# POWER.net
KiCad netlist of a schematic drawn in Altium Designer
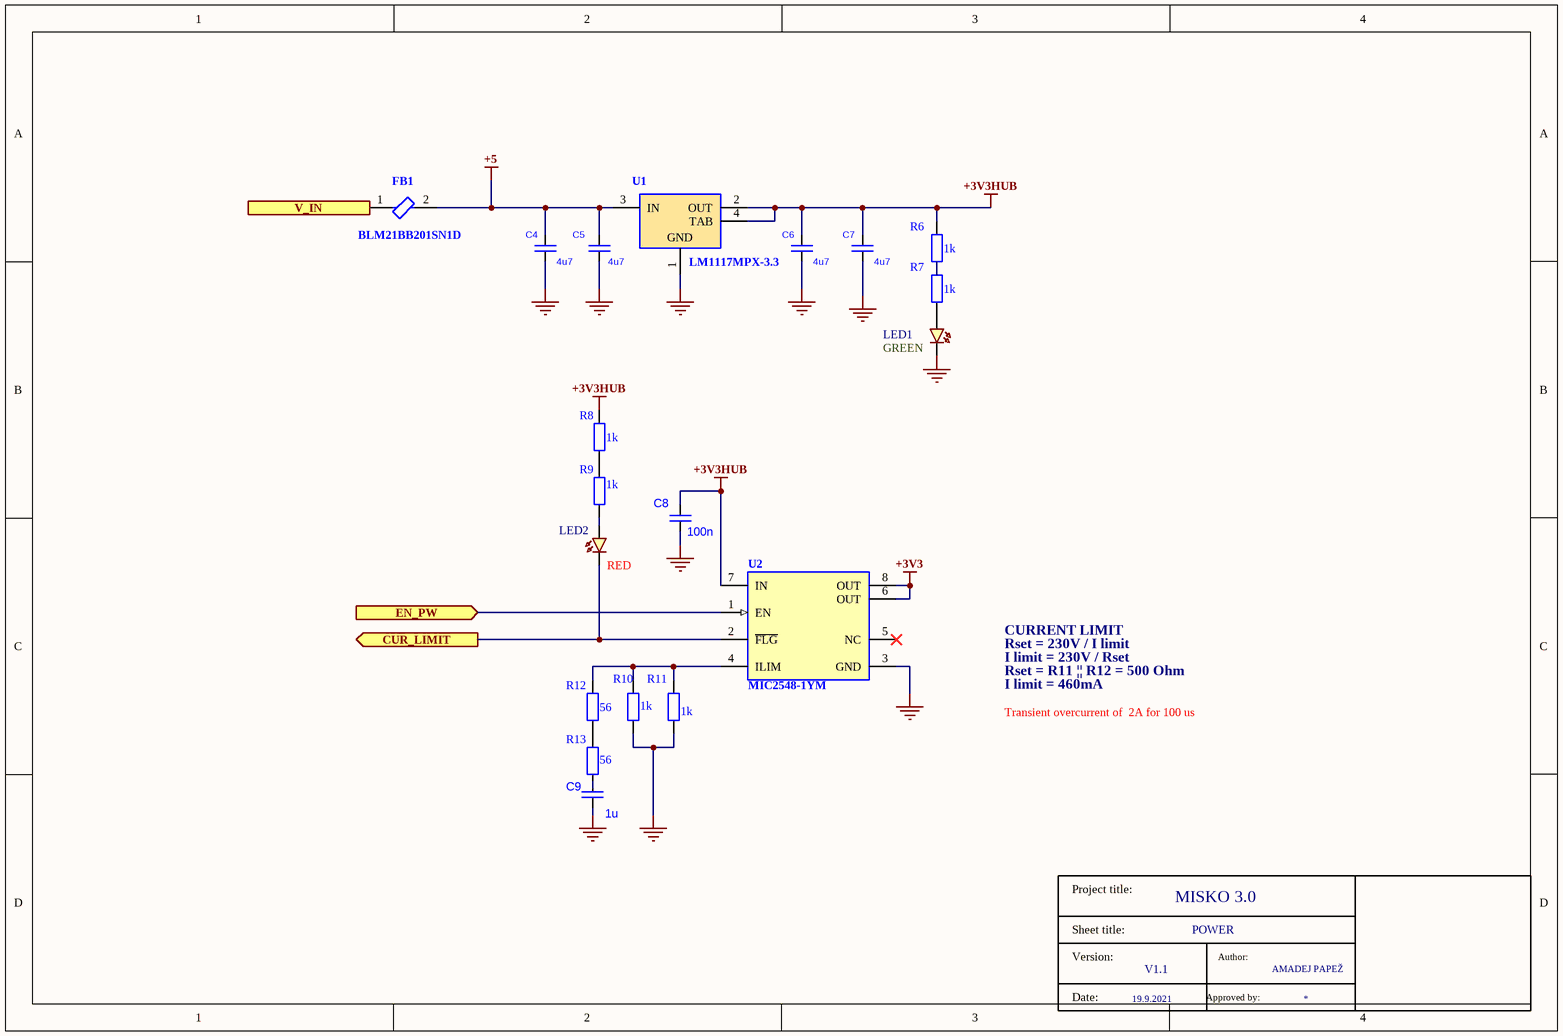
[diagram p0: POWER.SchDoc]

(export (version "E")
  (design (tool "Eeschema 10.0.6"))
  (components
    (comp (ref "C4")
      (value "4u7")
      (footprint "C0603")
      (description "Capacitor")
      (libsource (lib "MISKO3_V6") (part "C"))
    )
    (comp (ref "C5")
      (value "4u7")
      (footprint "C0603")
      (description "Capacitor")
      (libsource (lib "MISKO3_V6") (part "C"))
    )
    (comp (ref "C6")
      (value "4u7")
      (footprint "C0603")
      (description "Capacitor")
      (libsource (lib "MISKO3_V6") (part "C"))
    )
    (comp (ref "C7")
      (value "4u7")
      (footprint "C0603")
      (description "Capacitor")
      (libsource (lib "MISKO3_V6") (part "C"))
    )
    (comp (ref "C8")
      (value "100n")
      (footprint "C0603")
      (description "Capacitor")
      (libsource (lib "MISKO3_V6") (part "C"))
    )
    (comp (ref "C9")
      (value "1u")
      (footprint "C0603")
      (description "Capacitor")
      (libsource (lib "MISKO3_V6") (part "C"))
    )
    (comp (ref "FB1")
      (value "BLM21BB201SN1D")
      (footprint "BLM2102FB0805")
      (description "Chip Ferrite Bead, 0805, 200Ω @ 100MHz, 0.26Ω, 25%, 500mA")
      (fields (field (name "TOLERANCE") "25%"))
      (libsource (lib "MISKO3_V6") (part "BLM21BB201SN1D"))
    )
    (comp (ref "LED1")
      (value "GREEN")
      (footprint "LED0603")
      (description "Green light-emitting diode")
      (libsource (lib "MISKO3_V6") (part "LED"))
    )
    (comp (ref "LED2")
      (value "RED")
      (footprint "LED0603")
      (description "Red light-emitting diode")
      (libsource (lib "MISKO3_V6") (part "LED"))
    )
    (comp (ref "R6")
      (value "1k")
      (footprint "R1608_0603I_L")
      (description "R")
      (libsource (lib "MISKO3_V6") (part "R"))
    )
    (comp (ref "R7")
      (value "1k")
      (footprint "R1608_0603I_L")
      (description "R")
      (libsource (lib "MISKO3_V6") (part "R"))
    )
    (comp (ref "R8")
      (value "1k")
      (footprint "R1608_0603I_L")
      (description "R")
      (libsource (lib "MISKO3_V6") (part "R"))
    )
    (comp (ref "R9")
      (value "1k")
      (footprint "R1608_0603I_L")
      (description "R")
      (libsource (lib "MISKO3_V6") (part "R"))
    )
    (comp (ref "R10")
      (value "1k")
      (footprint "R1608_0603I_L")
      (description "R")
      (libsource (lib "MISKO3_V6") (part "R"))
    )
    (comp (ref "R11")
      (value "1k")
      (footprint "R1608_0603I_L")
      (description "R")
      (libsource (lib "MISKO3_V6") (part "R"))
    )
    (comp (ref "R12")
      (value "56")
      (footprint "R1608_0603I_L")
      (description "R")
      (libsource (lib "MISKO3_V6") (part "R"))
    )
    (comp (ref "R13")
      (value "56")
      (footprint "R1608_0603I_L")
      (description "R")
      (libsource (lib "MISKO3_V6") (part "R"))
    )
    (comp (ref "T3") (value "~") (libsource (lib "MISKO3_V6") (part "Title block")))
    (comp (ref "U1")
      (value "LM1117MPX-3.3")
      (footprint "DCY0004A_M")
      (fields
        (field (name "PARTNUMBER") "LM1117MPX-3.3/NOPB")
        (field (name "MANUFACTURER") "Texas Instruments")
      )
      (libsource (lib "MISKO3_V6") (part "LM1117MPX-3.3"))
    )
    (comp (ref "U2")
      (value "MIC2548-1YM")
      (footprint "SOIC_8_MIC2544")
      (fields
        (field (name "MANUFACTURER") "Microchip")
        (field (name "MANUFACTURER PART NUMBER") "MIC2544-1YMM-TR")
      )
      (libsource (lib "MISKO3_V6") (part "MIC2544-1YM"))
    )
  )
  (nets
    (net (code "1") (name "+3V3") (class "Default")
      (node (ref "U2") (pin "6") (pinfunction "OUT_6") (pintype "power_in"))
      (node (ref "U2") (pin "8") (pinfunction "OUT_8") (pintype "power_in"))
    )
    (net (code "2") (name "+3V3HUB") (class "Default")
      (node (ref "C6") (pin "2") (pinfunction "2_2") (pintype "passive"))
      (node (ref "C7") (pin "2") (pinfunction "2_2") (pintype "passive"))
      (node (ref "C8") (pin "2") (pinfunction "2_2") (pintype "passive"))
      (node (ref "R6") (pin "1") (pintype "passive"))
      (node (ref "R8") (pin "2") (pintype "passive"))
      (node (ref "U1") (pin "2") (pinfunction "OUT_2") (pintype "power_in"))
      (node (ref "U1") (pin "4") (pinfunction "TAB_4") (pintype "power_in"))
      (node (ref "U2") (pin "7") (pinfunction "IN_7") (pintype "power_in"))
    )
    (net (code "3") (name "+5") (class "Default")
      (node (ref "C4") (pin "2") (pinfunction "2_2") (pintype "passive"))
      (node (ref "C5") (pin "2") (pinfunction "2_2") (pintype "passive"))
      (node (ref "FB1") (pin "2") (pinfunction "2_2") (pintype "passive"))
      (node (ref "U1") (pin "3") (pinfunction "IN_3") (pintype "power_in"))
    )
    (net (code "4") (name "/CUR_LIMIT") (class "Default")
      (node (ref "LED2") (pin "1") (pinfunction "KATODE_1") (pintype "passive"))
      (node (ref "U2") (pin "2") (pinfunction "~{FLG}_2") (pintype "open_collector"))
    )
    (net (code "5") (name "/EN_PW") (class "Default")
      (node (ref "U2") (pin "1") (pinfunction "EN_1") (pintype "input"))
    )
    (net (code "6") (name "/V_IN") (class "Default")
      (node (ref "FB1") (pin "1") (pinfunction "1_1") (pintype "passive"))
    )
    (net (code "7") (name "GND") (class "Default")
      (node (ref "C4") (pin "1") (pinfunction "1_1") (pintype "passive"))
      (node (ref "C5") (pin "1") (pinfunction "1_1") (pintype "passive"))
      (node (ref "C6") (pin "1") (pinfunction "1_1") (pintype "passive"))
      (node (ref "C7") (pin "1") (pinfunction "1_1") (pintype "passive"))
      (node (ref "C8") (pin "1") (pinfunction "1_1") (pintype "passive"))
      (node (ref "C9") (pin "1") (pinfunction "1_1") (pintype "passive"))
      (node (ref "LED1") (pin "1") (pinfunction "KATODE_1") (pintype "passive"))
      (node (ref "R10") (pin "1") (pintype "passive"))
      (node (ref "R11") (pin "1") (pintype "passive"))
      (node (ref "U1") (pin "1") (pinfunction "GND_1") (pintype "power_in"))
      (node (ref "U2") (pin "3") (pinfunction "GND_3") (pintype "power_in"))
    )
    (net (code "8") (name "Net-(C9-Pad2)") (class "Default")
      (node (ref "C9") (pin "2") (pinfunction "2_2") (pintype "passive"))
      (node (ref "R13") (pin "1") (pintype "passive"))
    )
    (net (code "9") (name "Net-(LED1-ANODE)") (class "Default")
      (node (ref "LED1") (pin "2") (pinfunction "ANODE_2") (pintype "passive"))
      (node (ref "R7") (pin "2") (pintype "passive"))
    )
    (net (code "10") (name "Net-(LED2-ANODE)") (class "Default")
      (node (ref "LED2") (pin "2") (pinfunction "ANODE_2") (pintype "passive"))
      (node (ref "R9") (pin "1") (pintype "passive"))
    )
    (net (code "11") (name "Net-(R6-Pad2)") (class "Default")
      (node (ref "R6") (pin "2") (pintype "passive"))
      (node (ref "R7") (pin "1") (pintype "passive"))
    )
    (net (code "12") (name "Net-(R8-Pad1)") (class "Default")
      (node (ref "R8") (pin "1") (pintype "passive"))
      (node (ref "R9") (pin "2") (pintype "passive"))
    )
    (net (code "13") (name "Net-(R12-Pad1)") (class "Default")
      (node (ref "R12") (pin "1") (pintype "passive"))
      (node (ref "R13") (pin "2") (pintype "passive"))
    )
    (net (code "14") (name "Net-(U2-ILIM)") (class "Default")
      (node (ref "R10") (pin "2") (pintype "passive"))
      (node (ref "R11") (pin "2") (pintype "passive"))
      (node (ref "R12") (pin "2") (pintype "passive"))
      (node (ref "U2") (pin "4") (pinfunction "ILIM_4") (pintype "passive"))
    )
    (net (code "15") (name "unconnected-(U2-NC-Pad5)") (class "Default")
      (node (ref "U2") (pin "5") (pinfunction "NC_5") (pintype "passive+no_connect"))
    )
  )
)
